# Injector_1_1v.net
KiCad netlist of a schematic drawn in EAGLE
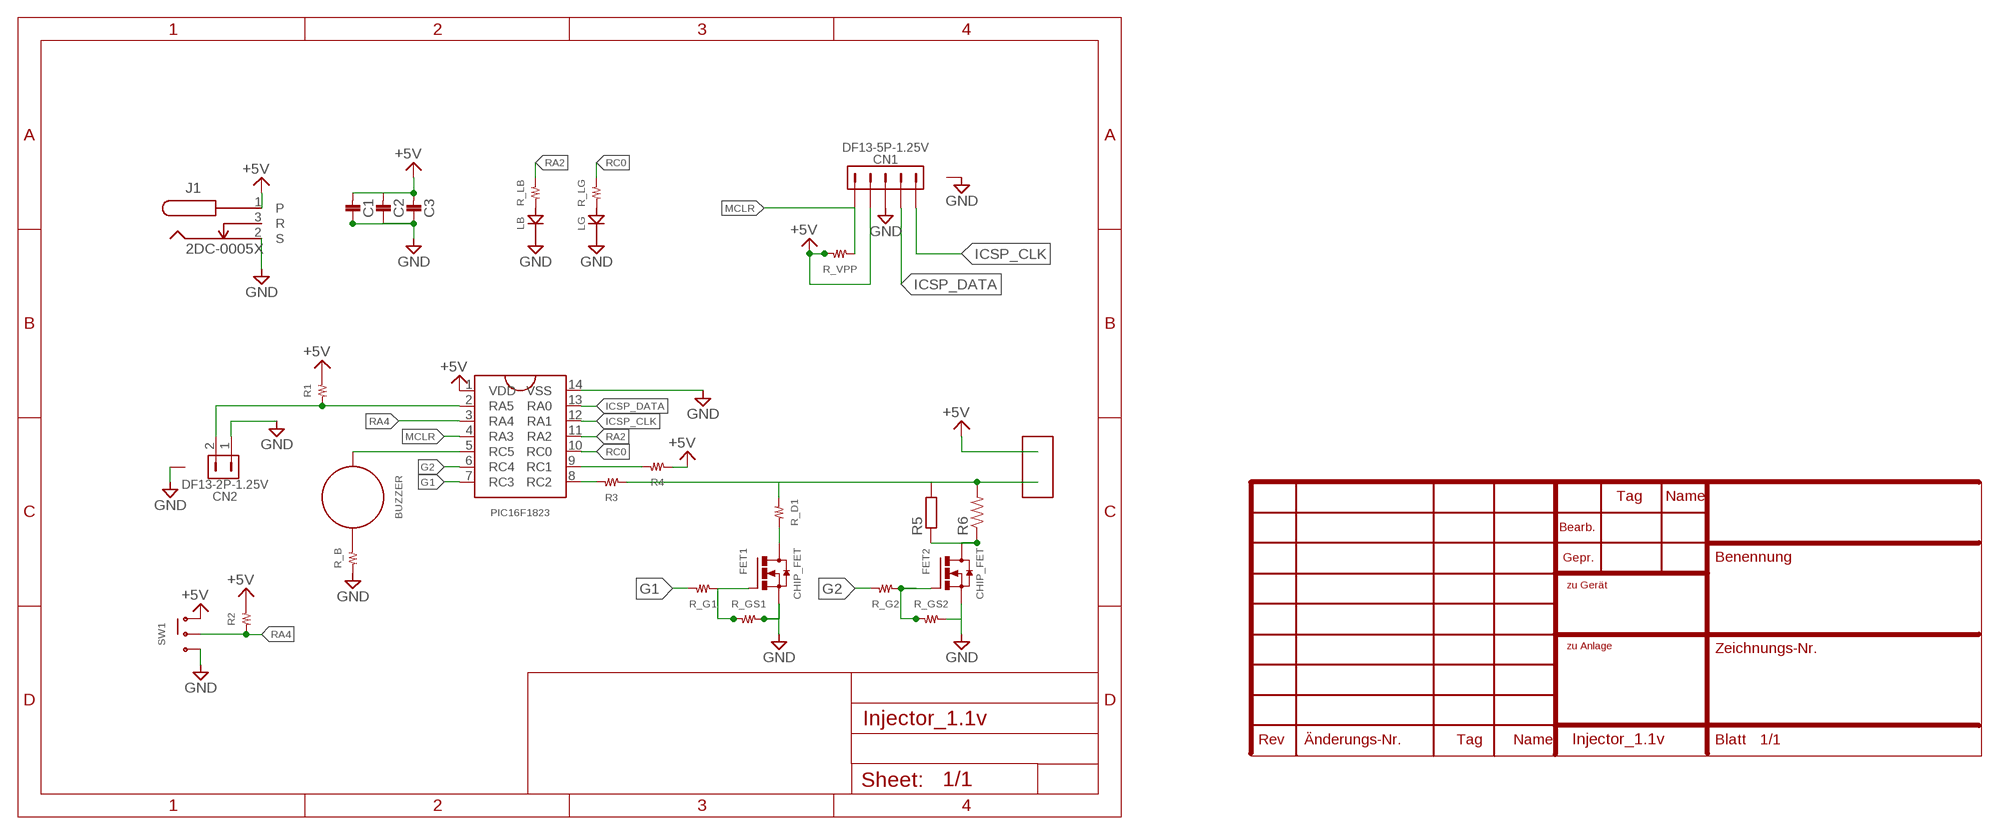
[diagram p0: schematic, sheet 1]

(export (version "E")
  (design (tool "Eeschema 10.0.6"))
  (components
    (comp (ref "BUZZER")
      (value "PKM13EPYH")
      (footprint "eagle-import:PKM13EPYH")
      (libsource (lib "eagle-import") (part "PKM13EPYH"))
    )
    (comp (ref "C1")
      (value "1608")
      (footprint "eagle-import:1608")
      (libsource (lib "eagle-import") (part "1608"))
    )
    (comp (ref "C2")
      (value "1608")
      (footprint "eagle-import:1608")
      (libsource (lib "eagle-import") (part "1608"))
    )
    (comp (ref "C3")
      (value "3225")
      (footprint "eagle-import:3225")
      (libsource (lib "eagle-import") (part "3225"))
    )
    (comp (ref "CN1")
      (value "DF13-5P-1.25V")
      (footprint "eagle-import:DF13C-5P-1.25V")
      (libsource (lib "eagle-import") (part "DF13-5P-1.25V"))
    )
    (comp (ref "CN2")
      (value "DF13-2P-1.25V")
      (footprint "eagle-import:DF13C-2P-1.25V")
      (libsource (lib "eagle-import") (part "DF13-2P-1.25V"))
    )
    (comp (ref "CN3")
      (value "PIN_HEADER_2")
      (footprint "eagle-import:PIN_HEADER_2S")
      (libsource (lib "eagle-import") (part "PIN_HEADER_2"))
    )
    (comp (ref "FET1")
      (value "CHIP_FET")
      (footprint "eagle-import:SOT23")
      (libsource (lib "eagle-import") (part "CHIP_FET"))
    )
    (comp (ref "FET2")
      (value "CHIP_FET")
      (footprint "eagle-import:SOT23")
      (libsource (lib "eagle-import") (part "CHIP_FET"))
    )
    (comp (ref "IC1")
      (value "PIC16F1823")
      (footprint "eagle-import:TSSOP")
      (libsource (lib "eagle-import") (part "PIC16F1823"))
    )
    (comp (ref "J1")
      (value "2DC-0005X")
      (footprint "eagle-import:2DC-0005D")
      (libsource (lib "eagle-import") (part "2DC-0005X"))
    )
    (comp (ref "LB")
      (value "CHIPLED")
      (footprint "eagle-import:1608")
      (libsource (lib "eagle-import") (part "CHIPLED"))
    )
    (comp (ref "LG")
      (value "CHIPLED")
      (footprint "eagle-import:1608")
      (libsource (lib "eagle-import") (part "CHIPLED"))
    )
    (comp (ref "R1")
      (value "RESISTOR__SMD")
      (footprint "eagle-import:1608")
      (libsource (lib "eagle-import") (part "RESISTOR__SMD"))
    )
    (comp (ref "R2")
      (value "RESISTOR__SMD")
      (footprint "eagle-import:1608")
      (libsource (lib "eagle-import") (part "RESISTOR__SMD"))
    )
    (comp (ref "R3")
      (value "RESISTOR__SMD")
      (footprint "eagle-import:1608")
      (libsource (lib "eagle-import") (part "RESISTOR__SMD"))
    )
    (comp (ref "R4")
      (value "RESISTOR__SMD")
      (footprint "eagle-import:1608")
      (libsource (lib "eagle-import") (part "RESISTOR__SMD"))
    )
    (comp (ref "R5")
      (value "R-EU_0411/12")
      (footprint "eagle-import:0411_12")
      (libsource (lib "eagle-import") (part "R-EU_0411/12"))
    )
    (comp (ref "R6")
      (value "R-US_0613/15")
      (footprint "eagle-import:P0613_15")
      (libsource (lib "eagle-import") (part "R-US_0613/15"))
    )
    (comp (ref "R_B")
      (value "RESISTOR__SMD")
      (footprint "eagle-import:1608")
      (libsource (lib "eagle-import") (part "RESISTOR__SMD"))
    )
    (comp (ref "R_D1")
      (value "RESISTOR__SMD")
      (footprint "eagle-import:1608")
      (libsource (lib "eagle-import") (part "RESISTOR__SMD"))
    )
    (comp (ref "R_G1")
      (value "RESISTOR__SMD")
      (footprint "eagle-import:1608")
      (libsource (lib "eagle-import") (part "RESISTOR__SMD"))
    )
    (comp (ref "R_G2")
      (value "RESISTOR__SMD")
      (footprint "eagle-import:1608")
      (libsource (lib "eagle-import") (part "RESISTOR__SMD"))
    )
    (comp (ref "R_GS1")
      (value "RESISTOR__SMD")
      (footprint "eagle-import:1608")
      (libsource (lib "eagle-import") (part "RESISTOR__SMD"))
    )
    (comp (ref "R_GS2")
      (value "RESISTOR__SMD")
      (footprint "eagle-import:1608")
      (libsource (lib "eagle-import") (part "RESISTOR__SMD"))
    )
    (comp (ref "R_LB")
      (value "RESISTOR__SMD")
      (footprint "eagle-import:1608")
      (libsource (lib "eagle-import") (part "RESISTOR__SMD"))
    )
    (comp (ref "R_LG")
      (value "RESISTOR__SMD")
      (footprint "eagle-import:1608")
      (libsource (lib "eagle-import") (part "RESISTOR__SMD"))
    )
    (comp (ref "R_VPP")
      (value "RESISTOR__SMD")
      (footprint "eagle-import:1608")
      (libsource (lib "eagle-import") (part "RESISTOR__SMD"))
    )
    (comp (ref "SW1")
      (value "SSSS213202")
      (footprint "eagle-import:SSSS2")
      (libsource (lib "eagle-import") (part "SSSS213202"))
    )
  )
  (nets
    (net (code "1") (name "+5V") (class "Default")
      (node (ref "C1") (pin "P$2") (pinfunction "2_P$2") (pintype "passive"))
      (node (ref "C2") (pin "P$2") (pinfunction "2_P$2") (pintype "passive"))
      (node (ref "C3") (pin "P$2") (pinfunction "2_P$2") (pintype "passive"))
      (node (ref "CN1") (pin "P$2") (pinfunction "2_P$2") (pintype "passive"))
      (node (ref "CN3") (pin "P$2") (pinfunction "P$2_P$2") (pintype "bidirectional"))
      (node (ref "IC1") (pin "1") (pinfunction "VDD_1") (pintype "bidirectional"))
      (node (ref "J1") (pin "1") (pinfunction "P_1") (pintype "power_in"))
      (node (ref "R1") (pin "2") (pinfunction "P$2_2") (pintype "passive"))
      (node (ref "R2") (pin "2") (pinfunction "P$2_2") (pintype "passive"))
      (node (ref "R4") (pin "1") (pinfunction "P$1_1") (pintype "passive"))
      (node (ref "R_VPP") (pin "2") (pinfunction "P$2_2") (pintype "passive"))
      (node (ref "SW1") (pin "1") (pinfunction "P$1_1") (pintype "bidirectional"))
      (node (ref "SW1") (pin "1-") (pinfunction "P$1_1-") (pintype "bidirectional"))
    )
    (net (code "2") (name "G1") (class "Default")
      (node (ref "IC1") (pin "7") (pinfunction "RC3_7") (pintype "bidirectional"))
      (node (ref "R_G1") (pin "2") (pinfunction "P$2_2") (pintype "passive"))
    )
    (net (code "3") (name "G2") (class "Default")
      (node (ref "IC1") (pin "6") (pinfunction "RC4_6") (pintype "bidirectional"))
      (node (ref "R_G2") (pin "2") (pinfunction "P$2_2") (pintype "passive"))
    )
    (net (code "4") (name "GND") (class "Default")
      (node (ref "C1") (pin "P$1") (pinfunction "1_P$1") (pintype "passive"))
      (node (ref "C2") (pin "P$1") (pinfunction "1_P$1") (pintype "passive"))
      (node (ref "C3") (pin "P$1") (pinfunction "1_P$1") (pintype "passive"))
      (node (ref "CN1") (pin "M$0") (pinfunction "G_M$0") (pintype "bidirectional"))
      (node (ref "CN1") (pin "M$1") (pinfunction "G_M$1") (pintype "bidirectional"))
      (node (ref "CN1") (pin "P$3") (pinfunction "3_P$3") (pintype "passive"))
      (node (ref "CN1") (pin "P$6") (pinfunction "G_P$6") (pintype "bidirectional"))
      (node (ref "CN1") (pin "P$7") (pinfunction "G_P$7") (pintype "bidirectional"))
      (node (ref "CN2") (pin "1") (pinfunction "1_1") (pintype "passive"))
      (node (ref "CN2") (pin "G1") (pinfunction "G_G1") (pintype "bidirectional"))
      (node (ref "CN2") (pin "G2") (pinfunction "G_G2") (pintype "bidirectional"))
      (node (ref "CN2") (pin "M$0") (pinfunction "G_M$0") (pintype "bidirectional"))
      (node (ref "CN2") (pin "M$1") (pinfunction "G_M$1") (pintype "bidirectional"))
      (node (ref "FET1") (pin "2") (pinfunction "S_2") (pintype "passive"))
      (node (ref "FET2") (pin "2") (pinfunction "S_2") (pintype "passive"))
      (node (ref "IC1") (pin "14") (pinfunction "VSS_14") (pintype "bidirectional"))
      (node (ref "J1") (pin "2") (pinfunction "S_2") (pintype "power_in"))
      (node (ref "LB") (pin "2") (pinfunction "K_2") (pintype "bidirectional"))
      (node (ref "LG") (pin "2") (pinfunction "K_2") (pintype "bidirectional"))
      (node (ref "R_B") (pin "1") (pinfunction "P$1_1") (pintype "passive"))
      (node (ref "R_GS1") (pin "2") (pinfunction "P$2_2") (pintype "passive"))
      (node (ref "R_GS2") (pin "2") (pinfunction "P$2_2") (pintype "passive"))
      (node (ref "SW1") (pin "3") (pinfunction "P$3_3") (pintype "bidirectional"))
      (node (ref "SW1") (pin "3-") (pinfunction "P$3_3-") (pintype "bidirectional"))
    )
    (net (code "5") (name "ICSP_CLK") (class "Default")
      (node (ref "CN1") (pin "P$5") (pinfunction "5_P$5") (pintype "passive"))
      (node (ref "IC1") (pin "12") (pinfunction "RA1_12") (pintype "bidirectional"))
    )
    (net (code "6") (name "ICSP_DATA") (class "Default")
      (node (ref "CN1") (pin "P$4") (pinfunction "4_P$4") (pintype "passive"))
      (node (ref "IC1") (pin "13") (pinfunction "RA0_13") (pintype "bidirectional"))
    )
    (net (code "7") (name "MCLR") (class "Default")
      (node (ref "CN1") (pin "P$1") (pinfunction "1_P$1") (pintype "passive"))
      (node (ref "IC1") (pin "4") (pinfunction "RA3_4") (pintype "bidirectional"))
      (node (ref "R_VPP") (pin "1") (pinfunction "P$1_1") (pintype "passive"))
    )
    (net (code "8") (name "Net-(FET1-D)") (class "Default")
      (node (ref "FET1") (pin "3") (pinfunction "D_3") (pintype "passive"))
      (node (ref "R_D1") (pin "2") (pinfunction "P$2_2") (pintype "passive"))
    )
    (net (code "9") (name "Net-(FET1-G)") (class "Default")
      (node (ref "FET1") (pin "1") (pinfunction "G_1") (pintype "passive"))
      (node (ref "R_G1") (pin "1") (pinfunction "P$1_1") (pintype "passive"))
      (node (ref "R_GS1") (pin "1") (pinfunction "P$1_1") (pintype "passive"))
    )
    (net (code "10") (name "Net-(FET2-D)") (class "Default")
      (node (ref "FET2") (pin "3") (pinfunction "D_3") (pintype "passive"))
      (node (ref "R5") (pin "1") (pinfunction "1_1") (pintype "passive"))
      (node (ref "R6") (pin "1") (pinfunction "1_1") (pintype "passive"))
    )
    (net (code "11") (name "Net-(FET2-G)") (class "Default")
      (node (ref "FET2") (pin "1") (pinfunction "G_1") (pintype "passive"))
      (node (ref "R_G2") (pin "1") (pinfunction "P$1_1") (pintype "passive"))
      (node (ref "R_GS2") (pin "1") (pinfunction "P$1_1") (pintype "passive"))
    )
    (net (code "12") (name "Net-(IC1-RA5)") (class "Default")
      (node (ref "CN2") (pin "2") (pinfunction "2_2") (pintype "passive"))
      (node (ref "IC1") (pin "2") (pinfunction "RA5_2") (pintype "bidirectional"))
      (node (ref "R1") (pin "1") (pinfunction "P$1_1") (pintype "passive"))
    )
    (net (code "13") (name "Net-(IC1-RC1)") (class "Default")
      (node (ref "IC1") (pin "9") (pinfunction "RC1_9") (pintype "bidirectional"))
      (node (ref "R4") (pin "2") (pinfunction "P$2_2") (pintype "passive"))
    )
    (net (code "14") (name "Net-(IC1-RC2)") (class "Default")
      (node (ref "IC1") (pin "8") (pinfunction "RC2_8") (pintype "bidirectional"))
      (node (ref "R3") (pin "2") (pinfunction "P$2_2") (pintype "passive"))
    )
    (net (code "15") (name "Net-(IC1-RC5)") (class "Default")
      (node (ref "BUZZER") (pin "P$1") (pinfunction "P$1_P$1") (pintype "bidirectional"))
      (node (ref "IC1") (pin "5") (pinfunction "RC5_5") (pintype "bidirectional"))
    )
    (net (code "16") (name "Net-(LB-A)") (class "Default")
      (node (ref "LB") (pin "1") (pinfunction "A_1") (pintype "bidirectional"))
      (node (ref "R_LB") (pin "1") (pinfunction "P$1_1") (pintype "passive"))
    )
    (net (code "17") (name "Net-(LG-A)") (class "Default")
      (node (ref "LG") (pin "1") (pinfunction "A_1") (pintype "bidirectional"))
      (node (ref "R_LG") (pin "1") (pinfunction "P$1_1") (pintype "passive"))
    )
    (net (code "18") (name "Net-(R3-P$1)") (class "Default")
      (node (ref "CN3") (pin "P$1") (pinfunction "P$1_P$1") (pintype "bidirectional"))
      (node (ref "R3") (pin "1") (pinfunction "P$1_1") (pintype "passive"))
      (node (ref "R5") (pin "2") (pinfunction "2_2") (pintype "passive"))
      (node (ref "R6") (pin "2") (pinfunction "2_2") (pintype "passive"))
      (node (ref "R_D1") (pin "1") (pinfunction "P$1_1") (pintype "passive"))
    )
    (net (code "19") (name "Net-(R_B-P$2)") (class "Default")
      (node (ref "BUZZER") (pin "P$2") (pinfunction "P$2_P$2") (pintype "bidirectional"))
      (node (ref "R_B") (pin "2") (pinfunction "P$2_2") (pintype "passive"))
    )
    (net (code "20") (name "RA2") (class "Default")
      (node (ref "IC1") (pin "11") (pinfunction "RA2_11") (pintype "bidirectional"))
      (node (ref "R_LB") (pin "2") (pinfunction "P$2_2") (pintype "passive"))
    )
    (net (code "21") (name "RA4") (class "Default")
      (node (ref "IC1") (pin "3") (pinfunction "RA4_3") (pintype "bidirectional"))
      (node (ref "R2") (pin "1") (pinfunction "P$1_1") (pintype "passive"))
      (node (ref "SW1") (pin "2") (pinfunction "P$2_2") (pintype "bidirectional"))
      (node (ref "SW1") (pin "2-") (pinfunction "P$2_2-") (pintype "bidirectional"))
    )
    (net (code "22") (name "RC0") (class "Default")
      (node (ref "IC1") (pin "10") (pinfunction "RC0_10") (pintype "bidirectional"))
      (node (ref "R_LG") (pin "2") (pinfunction "P$2_2") (pintype "passive"))
    )
    (net (code "23") (name "unconnected-(J1-R-Pad3)") (class "Default")
      (node (ref "J1") (pin "3") (pinfunction "R_3") (pintype "input"))
    )
  )
)
